# WINGS_SIGNAL_NODE_SCH.net
KiCad netlist of a schematic drawn in Altium Designer
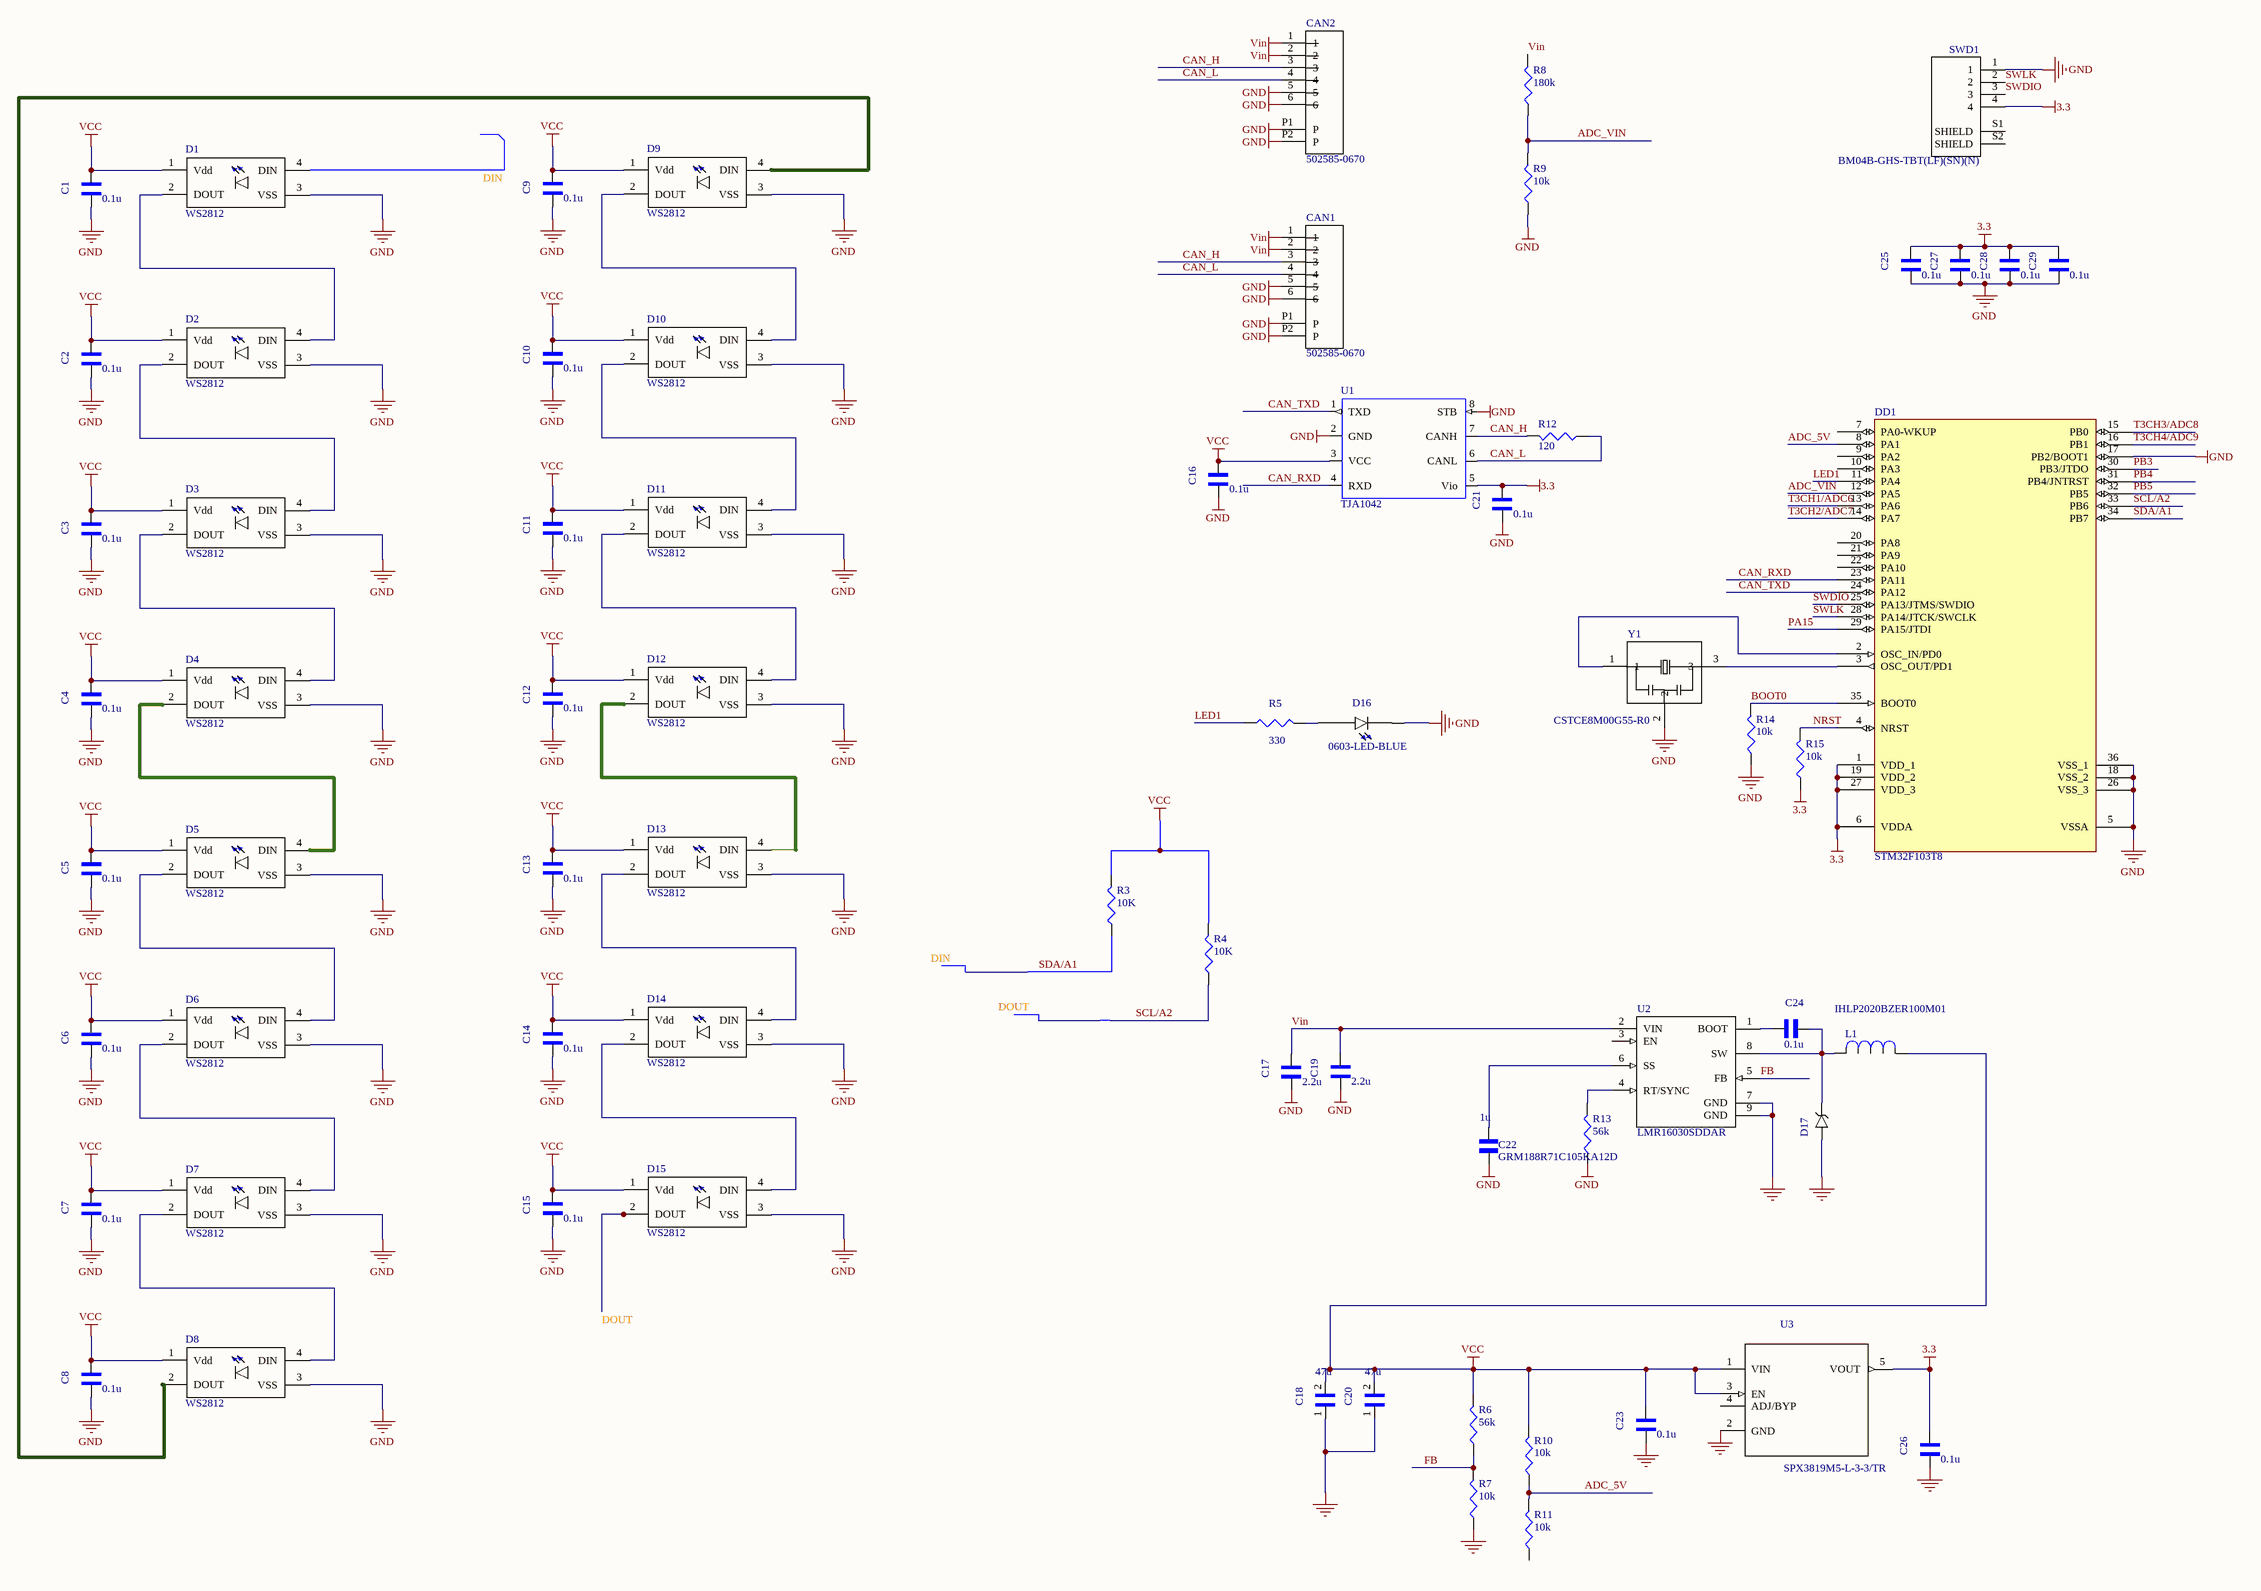
[diagram p0: WINGS_SIGNAL_NODE_SCH.SchDoc]

(export (version "E")
  (design (tool "Eeschema 10.0.6"))
  (components
    (comp (ref "C1")
      (value "0.1u")
      (footprint "*CAPC1608X90")
      (description "Cap Thin Film 0.1uf 50v 0603")
      (fields (field (name "MF") "AVX") (field (name "MP") "GX035C104MAT2-500 or CL10B104JB8NNNC"))
      (libsource (lib "lib") (part "GX035C104MAT2-500"))
    )
    (comp (ref "C2")
      (value "0.1u")
      (footprint "*CAPC1608X90")
      (description "Cap Thin Film 0.1uf 50v 0603")
      (fields (field (name "MF") "AVX") (field (name "MP") "GX035C104MAT2-500 or CL10B104JB8NNNC"))
      (libsource (lib "lib") (part "GX035C104MAT2-500"))
    )
    (comp (ref "C3")
      (value "0.1u")
      (footprint "*CAPC1608X90")
      (description "Cap Thin Film 0.1uf 50v 0603")
      (fields (field (name "MF") "AVX") (field (name "MP") "GX035C104MAT2-500 or CL10B104JB8NNNC"))
      (libsource (lib "lib") (part "GX035C104MAT2-500"))
    )
    (comp (ref "C4")
      (value "0.1u")
      (footprint "*CAPC1608X90")
      (description "Cap Thin Film 0.1uf 50v 0603")
      (fields (field (name "MF") "AVX") (field (name "MP") "GX035C104MAT2-500 or CL10B104JB8NNNC"))
      (libsource (lib "lib") (part "GX035C104MAT2-500"))
    )
    (comp (ref "C5")
      (value "0.1u")
      (footprint "*CAPC1608X90")
      (description "Cap Thin Film 0.1uf 50v 0603")
      (fields (field (name "MF") "AVX") (field (name "MP") "GX035C104MAT2-500 or CL10B104JB8NNNC"))
      (libsource (lib "lib") (part "GX035C104MAT2-500"))
    )
    (comp (ref "C6")
      (value "0.1u")
      (footprint "*CAPC1608X90")
      (description "Cap Thin Film 0.1uf 50v 0603")
      (fields (field (name "MF") "AVX") (field (name "MP") "GX035C104MAT2-500 or CL10B104JB8NNNC"))
      (libsource (lib "lib") (part "GX035C104MAT2-500"))
    )
    (comp (ref "C7")
      (value "0.1u")
      (footprint "*CAPC1608X90")
      (description "Cap Thin Film 0.1uf 50v 0603")
      (fields (field (name "MF") "AVX") (field (name "MP") "GX035C104MAT2-500 or CL10B104JB8NNNC"))
      (libsource (lib "lib") (part "GX035C104MAT2-500"))
    )
    (comp (ref "C8")
      (value "0.1u")
      (footprint "*CAPC1608X90")
      (description "Cap Thin Film 0.1uf 50v 0603")
      (fields (field (name "MF") "AVX") (field (name "MP") "GX035C104MAT2-500 or CL10B104JB8NNNC"))
      (libsource (lib "lib") (part "GX035C104MAT2-500"))
    )
    (comp (ref "C9")
      (value "0.1u")
      (footprint "*CAPC1608X90")
      (description "Cap Thin Film 0.1uf 50v 0603")
      (fields (field (name "MF") "AVX") (field (name "MP") "GX035C104MAT2-500 or CL10B104JB8NNNC"))
      (libsource (lib "lib") (part "GX035C104MAT2-500"))
    )
    (comp (ref "C10")
      (value "0.1u")
      (footprint "*CAPC1608X90")
      (description "Cap Thin Film 0.1uf 50v 0603")
      (fields (field (name "MF") "AVX") (field (name "MP") "GX035C104MAT2-500 or CL10B104JB8NNNC"))
      (libsource (lib "lib") (part "GX035C104MAT2-500"))
    )
    (comp (ref "C11")
      (value "0.1u")
      (footprint "*CAPC1608X90")
      (description "Cap Thin Film 0.1uf 50v 0603")
      (fields (field (name "MF") "AVX") (field (name "MP") "GX035C104MAT2-500 or CL10B104JB8NNNC"))
      (libsource (lib "lib") (part "GX035C104MAT2-500"))
    )
    (comp (ref "C12")
      (value "0.1u")
      (footprint "*CAPC1608X90")
      (description "Cap Thin Film 0.1uf 50v 0603")
      (fields (field (name "MF") "AVX") (field (name "MP") "GX035C104MAT2-500 or CL10B104JB8NNNC"))
      (libsource (lib "lib") (part "GX035C104MAT2-500"))
    )
    (comp (ref "C13")
      (value "0.1u")
      (footprint "*CAPC1608X90")
      (description "Cap Thin Film 0.1uf 50v 0603")
      (fields (field (name "MF") "AVX") (field (name "MP") "GX035C104MAT2-500 or CL10B104JB8NNNC"))
      (libsource (lib "lib") (part "GX035C104MAT2-500"))
    )
    (comp (ref "C14")
      (value "0.1u")
      (footprint "*CAPC1608X90")
      (description "Cap Thin Film 0.1uf 50v 0603")
      (fields (field (name "MF") "AVX") (field (name "MP") "GX035C104MAT2-500 or CL10B104JB8NNNC"))
      (libsource (lib "lib") (part "GX035C104MAT2-500"))
    )
    (comp (ref "C15")
      (value "0.1u")
      (footprint "*CAPC1608X90")
      (description "Cap Thin Film 0.1uf 50v 0603")
      (fields (field (name "MF") "AVX") (field (name "MP") "GX035C104MAT2-500 or CL10B104JB8NNNC"))
      (libsource (lib "lib") (part "GX035C104MAT2-500"))
    )
    (comp (ref "C16")
      (value "0.1u")
      (footprint "*CAPC1608X90")
      (description "Cap Thin Film 0.1uf 50v 0603")
      (fields (field (name "MF") "AVX") (field (name "MP") "GX035C104MAT2-500 or CL10B104JB8NNNC"))
      (libsource (lib "lib") (part "GX035C104MAT2-500"))
    )
    (comp (ref "C17")
      (value "2.2u")
      (footprint "*CAP3216X125N")
      (description "1206 2.2 uF 50 V В±10% Tolerance X7R SMT Multilayer Ceramic Capacitor")
      (fields (field (name "MF") "Murata Electronics") (field (name "MP") "GRM31CR71H225KA88L"))
      (libsource (lib "lib") (part "GRM31CR71H225KA88L"))
    )
    (comp (ref "C18")
      (value "47u")
      (footprint "*CAPC3216X125N")
      (description "Multilayer Ceramic Capacitor, GRM Series, 47 - F, - 10%, X5R, 10 V, 1206 [3216 Metric]")
      (fields (field (name "MF") "Murata Electronics") (field (name "MP") "GRM31CR61A476KE15L"))
      (libsource (lib "lib") (part "GRM31CR61A476KE15L"))
    )
    (comp (ref "C19")
      (value "2.2u")
      (footprint "*CAP3216X125N")
      (description "1206 2.2 uF 50 V В±10% Tolerance X7R SMT Multilayer Ceramic Capacitor")
      (fields (field (name "MF") "Murata Electronics") (field (name "MP") "GRM31CR71H225KA88L"))
      (libsource (lib "lib") (part "GRM31CR71H225KA88L"))
    )
    (comp (ref "C20")
      (value "47u")
      (footprint "*CAPC3216X125N")
      (description "Multilayer Ceramic Capacitor, GRM Series, 47 - F, - 10%, X5R, 10 V, 1206 [3216 Metric]")
      (fields (field (name "MF") "Murata Electronics") (field (name "MP") "GRM31CR61A476KE15L"))
      (libsource (lib "lib") (part "GRM31CR61A476KE15L"))
    )
    (comp (ref "C21")
      (value "0.1u")
      (footprint "*CAPC1608X90")
      (description "Cap Thin Film 0.1uf 50v 0603")
      (fields (field (name "MF") "AVX") (field (name "MP") "GX035C104MAT2-500 or CL10B104JB8NNNC"))
      (libsource (lib "lib") (part "GX035C104MAT2-500"))
    )
    (comp (ref "C22")
      (value "GRM188R71C105KA12D")
      (footprint "CAPC1608X90N")
      (description "SMD Capacitor X7R(EIA) with Capacitance: 1.0uF Tol. 10%. Rated Voltage: 16Vdc")
      (fields (field (name "MF") "Murata Electronics") (field (name "ALTIUM_VALUE") "1u"))
      (libsource (lib "lib") (part "GRM188R71C105KA12D"))
    )
    (comp (ref "C23")
      (value "0.1u")
      (footprint "*CAPC1608X90")
      (description "Cap Thin Film 0.1uf 50v 0603")
      (fields (field (name "MF") "AVX") (field (name "MP") "GX035C104MAT2-500"))
      (libsource (lib "lib") (part "GX035C104MAT2-500"))
    )
    (comp (ref "C24")
      (value "0.1u")
      (footprint "*CAPC1608X90")
      (description "Cap Thin Film 0.1uf 50v 0603")
      (fields (field (name "MF") "AVX") (field (name "MP") "GX035C104MAT2-500 or CL10B104JB8NNNC"))
      (libsource (lib "lib") (part "GX035C104MAT2-500"))
    )
    (comp (ref "C25")
      (value "0.1u")
      (footprint "*CAPC1608X90")
      (description "Cap Thin Film 0.1uf 50v 0603")
      (fields (field (name "MF") "AVX") (field (name "MP") "GX035C104MAT2-500 or CL10B104JB8NNNC"))
      (libsource (lib "lib") (part "GX035C104MAT2-500"))
    )
    (comp (ref "C26")
      (value "0.1u")
      (footprint "*CAPC1608X90")
      (description "Cap Thin Film 0.1uf 50v 0603")
      (fields (field (name "MF") "AVX") (field (name "MP") "GX035C104MAT2-500"))
      (libsource (lib "lib") (part "GX035C104MAT2-500"))
    )
    (comp (ref "C27")
      (value "0.1u")
      (footprint "*CAPC1608X90")
      (description "Cap Thin Film 0.1uf 50v 0603")
      (fields (field (name "MF") "AVX") (field (name "MP") "GX035C104MAT2-500 or CL10B104JB8NNNC"))
      (libsource (lib "lib") (part "GX035C104MAT2-500"))
    )
    (comp (ref "C28")
      (value "0.1u")
      (footprint "*CAPC1608X90")
      (description "Cap Thin Film 0.1uf 50v 0603")
      (fields (field (name "MF") "AVX") (field (name "MP") "GX035C104MAT2-500 or CL10B104JB8NNNC"))
      (libsource (lib "lib") (part "GX035C104MAT2-500"))
    )
    (comp (ref "C29")
      (value "0.1u")
      (footprint "*CAPC1608X90")
      (description "Cap Thin Film 0.1uf 50v 0603")
      (fields (field (name "MF") "AVX") (field (name "MP") "GX035C104MAT2-500 or CL10B104JB8NNNC"))
      (libsource (lib "lib") (part "GX035C104MAT2-500"))
    )
    (comp (ref "CAN1")
      (value "502585-0670")
      (footprint "MOLEX_502585-0670")
      (fields (field (name "MF") "Molex"))
      (libsource (lib "lib") (part "502585-0670"))
    )
    (comp (ref "CAN2")
      (value "502585-0670")
      (footprint "MOLEX_502585-0670")
      (fields (field (name "MF") "Molex"))
      (libsource (lib "lib") (part "502585-0670"))
    )
    (comp (ref "D1")
      (value "WS2812")
      (footprint "LED_WS2812")
      (description "Addressable Lighting - 5 LED Discrete Serial _Shift Register_ Red, Green, Blue _RGB_ 5.00mm Dia")
      (fields (field (name "MF") "SparkFun Electronics"))
      (libsource (lib "lib") (part "WS2812"))
    )
    (comp (ref "D2")
      (value "WS2812")
      (footprint "LED_WS2812")
      (description "Addressable Lighting - 5 LED Discrete Serial _Shift Register_ Red, Green, Blue _RGB_ 5.00mm Dia")
      (fields (field (name "MF") "SparkFun Electronics"))
      (libsource (lib "lib") (part "WS2812"))
    )
    (comp (ref "D3")
      (value "WS2812")
      (footprint "LED_WS2812")
      (description "Addressable Lighting - 5 LED Discrete Serial _Shift Register_ Red, Green, Blue _RGB_ 5.00mm Dia")
      (fields (field (name "MF") "SparkFun Electronics"))
      (libsource (lib "lib") (part "WS2812"))
    )
    (comp (ref "D4")
      (value "WS2812")
      (footprint "LED_WS2812")
      (description "Addressable Lighting - 5 LED Discrete Serial _Shift Register_ Red, Green, Blue _RGB_ 5.00mm Dia")
      (fields (field (name "MF") "SparkFun Electronics"))
      (libsource (lib "lib") (part "WS2812"))
    )
    (comp (ref "D5")
      (value "WS2812")
      (footprint "LED_WS2812")
      (description "Addressable Lighting - 5 LED Discrete Serial _Shift Register_ Red, Green, Blue _RGB_ 5.00mm Dia")
      (fields (field (name "MF") "SparkFun Electronics"))
      (libsource (lib "lib") (part "WS2812"))
    )
    (comp (ref "D6")
      (value "WS2812")
      (footprint "LED_WS2812")
      (description "Addressable Lighting - 5 LED Discrete Serial _Shift Register_ Red, Green, Blue _RGB_ 5.00mm Dia")
      (fields (field (name "MF") "SparkFun Electronics"))
      (libsource (lib "lib") (part "WS2812"))
    )
    (comp (ref "D7")
      (value "WS2812")
      (footprint "LED_WS2812")
      (description "Addressable Lighting - 5 LED Discrete Serial _Shift Register_ Red, Green, Blue _RGB_ 5.00mm Dia")
      (fields (field (name "MF") "SparkFun Electronics"))
      (libsource (lib "lib") (part "WS2812"))
    )
    (comp (ref "D8")
      (value "WS2812")
      (footprint "LED_WS2812")
      (description "Addressable Lighting - 5 LED Discrete Serial _Shift Register_ Red, Green, Blue _RGB_ 5.00mm Dia")
      (fields (field (name "MF") "SparkFun Electronics"))
      (libsource (lib "lib") (part "WS2812"))
    )
    (comp (ref "D9")
      (value "WS2812")
      (footprint "LED_WS2812")
      (description "Addressable Lighting - 5 LED Discrete Serial _Shift Register_ Red, Green, Blue _RGB_ 5.00mm Dia")
      (fields (field (name "MF") "SparkFun Electronics"))
      (libsource (lib "lib") (part "WS2812"))
    )
    (comp (ref "D10")
      (value "WS2812")
      (footprint "LED_WS2812")
      (description "Addressable Lighting - 5 LED Discrete Serial _Shift Register_ Red, Green, Blue _RGB_ 5.00mm Dia")
      (fields (field (name "MF") "SparkFun Electronics"))
      (libsource (lib "lib") (part "WS2812"))
    )
    (comp (ref "D11")
      (value "WS2812")
      (footprint "LED_WS2812")
      (description "Addressable Lighting - 5 LED Discrete Serial _Shift Register_ Red, Green, Blue _RGB_ 5.00mm Dia")
      (fields (field (name "MF") "SparkFun Electronics"))
      (libsource (lib "lib") (part "WS2812"))
    )
    (comp (ref "D12")
      (value "WS2812")
      (footprint "LED_WS2812")
      (description "Addressable Lighting - 5 LED Discrete Serial _Shift Register_ Red, Green, Blue _RGB_ 5.00mm Dia")
      (fields (field (name "MF") "SparkFun Electronics"))
      (libsource (lib "lib") (part "WS2812"))
    )
    (comp (ref "D13")
      (value "WS2812")
      (footprint "LED_WS2812")
      (description "Addressable Lighting - 5 LED Discrete Serial _Shift Register_ Red, Green, Blue _RGB_ 5.00mm Dia")
      (fields (field (name "MF") "SparkFun Electronics"))
      (libsource (lib "lib") (part "WS2812"))
    )
    (comp (ref "D14")
      (value "WS2812")
      (footprint "LED_WS2812")
      (description "Addressable Lighting - 5 LED Discrete Serial _Shift Register_ Red, Green, Blue _RGB_ 5.00mm Dia")
      (fields (field (name "MF") "SparkFun Electronics"))
      (libsource (lib "lib") (part "WS2812"))
    )
    (comp (ref "D15")
      (value "WS2812")
      (footprint "LED_WS2812")
      (description "Addressable Lighting - 5 LED Discrete Serial _Shift Register_ Red, Green, Blue _RGB_ 5.00mm Dia")
      (fields (field (name "MF") "SparkFun Electronics"))
      (libsource (lib "lib") (part "WS2812"))
    )
    (comp (ref "D16")
      (value "0603-LED-BLUE")
      (footprint "*LEDM1608X80_LTE-C1906R-14(Primary)")
      (description "LED IrLED Chip LED 2-Pin SMD T/R")
      (libsource (lib "lib") (part "LTE-C1906R-14"))
    )
    (comp (ref "D17")
      (value "SK56")
      (footprint "*SMB_P6SMB62AT3G(Primary)")
      (description "Диод Шоттки 5А 60В [SMB / DO-214AA]")
      (fields (field (name "MF") "Littelfuse Inc."))
      (libsource (lib "lib") (part "SK56"))
    )
    (comp (ref "DD1")
      (value "STM32F103T8")
      (footprint "*QFN50P600X600X100-37N")
      (description "STM32F103T8U6, Микроконтроллер 32BIT ARM 64K FLASH [VFQFPN-36]")
      (fields (field (name "MF") "STM") (field (name "MP") "STM32F103T8U6"))
      (libsource (lib "lib") (part "STM32F103T8"))
    )
    (comp (ref "L1")
      (value "IHLP2020BZER100M01")
      (footprint "IHLP")
      (description "10ÂµH Shielded Molded Inductor 2.3A 199mOhm Max Nonstandard")
      (fields (field (name "MF") "Vishay Dale"))
      (libsource (lib "lib") (part "IHLP2020BZER100M01"))
    )
    (comp (ref "R3")
      (value "10K")
      (footprint "J1-0603")
      (description "Resistor")
      (fields (field (name "MP") "4.7K 1% 0603") (field (name "Comment") "Res3"))
      (libsource (lib "Miscellaneous Devices") (part "Res3"))
    )
    (comp (ref "R4")
      (value "10K")
      (footprint "J1-0603")
      (description "Resistor")
      (fields (field (name "MP") "4.7K 1% 0603") (field (name "Comment") "Res3"))
      (libsource (lib "Miscellaneous Devices") (part "Res3"))
    )
    (comp (ref "R5")
      (value "330")
      (footprint "J1-0603")
      (description "Resistor")
      (fields (field (name "MP") "RC0603FR-07330RL") (field (name "Comment") "Res3"))
      (libsource (lib "Miscellaneous Devices") (part "Res3"))
    )
    (comp (ref "R6")
      (value "56k")
      (footprint "J1-0603")
      (description "Resistor")
      (fields (field (name "MP") "RC0603FR-0756KL") (field (name "Comment") "Res3"))
      (libsource (lib "Miscellaneous Devices") (part "Res3"))
    )
    (comp (ref "R7")
      (value "10k")
      (footprint "J1-0603")
      (description "10 kOhms 1 0.1 W 1 10 W Chip Resistor 0603 1608 Metric Thick Film")
      (fields (field (name "MF") "Yageo or NXP") (field (name "MP") "10K 1% 0603"))
      (libsource (lib "CAN_NODE_MINI") (part "RC0603FR-0710KL"))
    )
    (comp (ref "R8")
      (value "180k")
      (footprint "J1-0603")
      (description "Resistor")
      (fields (field (name "MP") "180K 1% 0603") (field (name "Comment") "Res3"))
      (libsource (lib "Miscellaneous Devices") (part "Res3"))
    )
    (comp (ref "R9")
      (value "10k")
      (footprint "J1-0603")
      (description "Resistor")
      (fields (field (name "MP") "10K 1% 0603") (field (name "Comment") "Res3"))
      (libsource (lib "Miscellaneous Devices") (part "Res3"))
    )
    (comp (ref "R10")
      (value "10k")
      (footprint "J1-0603")
      (description "10 kOhms 1 0.1 W 1 10 W Chip Resistor 0603 1608 Metric Thick Film")
      (fields (field (name "MF") "Yageo or NXP") (field (name "MP") "10K 1% 0603"))
      (libsource (lib "CAN_NODE_MINI") (part "RC0603FR-0710KL"))
    )
    (comp (ref "R11")
      (value "10k")
      (footprint "J1-0603")
      (description "10 kOhms 1 0.1 W 1 10 W Chip Resistor 0603 1608 Metric Thick Film")
      (fields (field (name "MF") "Yageo or NXP") (field (name "MP") "10K 1% 0603"))
      (libsource (lib "CAN_NODE_MINI") (part "RC0603FR-0710KL"))
    )
    (comp (ref "R12")
      (value "120")
      (footprint "J1-0603")
      (description "120 Ohms 1 0.1 W 1 10 W Chip Resistor 0603 1608 Metric Thick Film")
      (fields (field (name "MP") "RC0603FR-07120RL") (field (name "Comment") "Res3"))
      (libsource (lib "Miscellaneous Devices") (part "Res3"))
    )
    (comp (ref "R13")
      (value "56k")
      (footprint "J1-0603")
      (description "Resistor")
      (fields (field (name "MP") "RC0603FR-0756KL") (field (name "Comment") "Res3"))
      (libsource (lib "Miscellaneous Devices") (part "Res3"))
    )
    (comp (ref "R14")
      (value "10k")
      (footprint "J1-0603")
      (description "10 kOhms 1 0.1 W 1 10 W Chip Resistor 0603 1608 Metric Thick Film")
      (fields (field (name "MF") "Yageo or NXP") (field (name "MP") "10K 1% 0603"))
      (libsource (lib "CAN_NODE_MINI") (part "RC0603FR-0710KL"))
    )
    (comp (ref "R15")
      (value "10k")
      (footprint "J1-0603")
      (description "10 kOhms 1 0.1 W 1 10 W Chip Resistor 0603 1608 Metric Thick Film")
      (fields (field (name "MF") "Yageo or NXP") (field (name "MP") "10K 1% 0603"))
      (libsource (lib "CAN_NODE_MINI") (part "RC0603FR-0710KL"))
    )
    (comp (ref "SWD1")
      (value "BM04B-GHS-TBT(LF)(SN)(N)")
      (footprint "JST_BM04B-GHS-holes")
      (description "Conn Shrouded Header HDR 4 POS 1.25mm Solder ST SMD Reel")
      (fields (field (name "MF") "JST Sales") (field (name "MP") "SM04B-GHS-TB(LF)(SN)"))
      (libsource (lib "lib") (part "BM04B-GHS-TBT(LF)(SN)(N)"))
    )
    (comp (ref "U1")
      (value "TJA1042")
      (footprint "SOT782-1")
      (description "1/1 Transceiver Half CANbus 8-SO")
      (fields (field (name "MF") "NXP USA"))
      (libsource (lib "lib") (part "TJA1042"))
    )
    (comp (ref "U2")
      (value "LMR16030SDDAR")
      (footprint "*SOIC127P600X170-9N - duplicate")
      (fields (field (name "MF") "Texas Instruments"))
      (libsource (lib "lib") (part "LMR16030SDDAR"))
    )
    (comp (ref "U3")
      (value "SPX3819M5-L-3-3/TR")
      (footprint "*SOT95P280X145-5N")
      (description "Low Dropout Voltage Regulator, Adjustable 0.5A, В±1%, 2.5 to 16 Vin, 5-Pin SOT-23")
      (fields (field (name "MF") "MaxLinear, Inc."))
      (libsource (lib "DC_DC") (part "SPX3819M5-L"))
    )
    (comp (ref "Y1")
      (value "CSTCE8M00G55-R0")
      (footprint "*OSC_CSTCE8M00G55-R0")
      (description "Ceramic Resonator 8MHz ??0.5% _Tol_ ??0.2% _Stability_ 33pF 40Ohm 3-Pin CSMD T/R")
      (fields (field (name "MF") "Murata"))
      (libsource (lib "DC_DC") (part "CSTCE8M00G55-R0"))
    )
  )
  (nets
    (net (code "1") (name "/ADC_5V") (class "Default")
      (node (ref "DD1") (pin "8") (pinfunction "PA1_8") (pintype "bidirectional"))
      (node (ref "R10") (pin "1") (pinfunction "1_1") (pintype "passive"))
      (node (ref "R11") (pin "2") (pinfunction "2_2") (pintype "passive"))
    )
    (net (code "2") (name "/ADC_VIN") (class "Default")
      (node (ref "DD1") (pin "12") (pinfunction "PA5_12") (pintype "bidirectional"))
      (node (ref "R8") (pin "1") (pinfunction "1_1") (pintype "passive"))
      (node (ref "R9") (pin "2") (pinfunction "2_2") (pintype "passive"))
    )
    (net (code "3") (name "/BOOT0") (class "Default")
      (node (ref "DD1") (pin "35") (pinfunction "BOOT0_35") (pintype "input"))
      (node (ref "R14") (pin "2") (pinfunction "2_2") (pintype "passive"))
    )
    (net (code "4") (name "/CAN_H") (class "Default")
      (node (ref "CAN1") (pin "3") (pinfunction "3_3") (pintype "passive"))
      (node (ref "CAN2") (pin "3") (pinfunction "3_3") (pintype "passive"))
      (node (ref "R12") (pin "2") (pinfunction "2_2") (pintype "passive"))
      (node (ref "U1") (pin "7") (pinfunction "CANH_7") (pintype "bidirectional"))
    )
    (net (code "5") (name "/CAN_L") (class "Default")
      (node (ref "CAN1") (pin "4") (pinfunction "4_4") (pintype "passive"))
      (node (ref "CAN2") (pin "4") (pinfunction "4_4") (pintype "passive"))
      (node (ref "R12") (pin "1") (pinfunction "1_1") (pintype "passive"))
      (node (ref "U1") (pin "6") (pinfunction "CANL_6") (pintype "bidirectional"))
    )
    (net (code "6") (name "/CAN_RXD") (class "Default")
      (node (ref "DD1") (pin "23") (pinfunction "PA11_23") (pintype "bidirectional"))
      (node (ref "U1") (pin "4") (pinfunction "RXD_4") (pintype "bidirectional"))
    )
    (net (code "7") (name "/CAN_TXD") (class "Default")
      (node (ref "DD1") (pin "24") (pinfunction "PA12_24") (pintype "bidirectional"))
      (node (ref "U1") (pin "1") (pinfunction "TXD_1") (pintype "output"))
    )
    (net (code "8") (name "/DIN") (class "Default")
      (node (ref "D1") (pin "4") (pinfunction "DIN_4") (pintype "power_in"))
      (node (ref "DD1") (pin "34") (pinfunction "PB7_34") (pintype "bidirectional"))
      (node (ref "R3") (pin "1") (pinfunction "1_1") (pintype "passive"))
    )
    (net (code "9") (name "/DOUT") (class "Default")
      (node (ref "D15") (pin "2") (pinfunction "DOUT_2") (pintype "power_in"))
      (node (ref "DD1") (pin "33") (pinfunction "PB6_33") (pintype "bidirectional"))
      (node (ref "R4") (pin "1") (pinfunction "1_1") (pintype "passive"))
    )
    (net (code "10") (name "/FB") (class "Default")
      (node (ref "R6") (pin "1") (pinfunction "1_1") (pintype "passive"))
      (node (ref "R7") (pin "2") (pinfunction "2_2") (pintype "passive"))
      (node (ref "U2") (pin "5") (pinfunction "FB_5") (pintype "input"))
    )
    (net (code "11") (name "/LED1") (class "Default")
      (node (ref "DD1") (pin "11") (pinfunction "PA4_11") (pintype "bidirectional"))
      (node (ref "R5") (pin "1") (pinfunction "1_1") (pintype "passive"))
    )
    (net (code "12") (name "/NRST") (class "Default")
      (node (ref "DD1") (pin "4") (pinfunction "NRST_4") (pintype "bidirectional"))
      (node (ref "R15") (pin "2") (pinfunction "2_2") (pintype "passive"))
    )
    (net (code "13") (name "/PA15") (class "Default")
      (node (ref "DD1") (pin "29") (pinfunction "PA15/JTDI_29") (pintype "bidirectional"))
    )
    (net (code "14") (name "/PB3") (class "Default")
      (node (ref "DD1") (pin "30") (pinfunction "PB3/JTDO_30") (pintype "bidirectional"))
    )
    (net (code "15") (name "/PB4") (class "Default")
      (node (ref "DD1") (pin "31") (pinfunction "PB4/JNTRST_31") (pintype "bidirectional"))
    )
    (net (code "16") (name "/PB5") (class "Default")
      (node (ref "DD1") (pin "32") (pinfunction "PB5_32") (pintype "bidirectional"))
    )
    (net (code "17") (name "/SWDIO") (class "Default")
      (node (ref "DD1") (pin "25") (pinfunction "PA13/JTMS/SWDIO_25") (pintype "bidirectional"))
      (node (ref "SWD1") (pin "3") (pinfunction "3_3") (pintype "passive"))
    )
    (net (code "18") (name "/SWLK") (class "Default")
      (node (ref "DD1") (pin "28") (pinfunction "PA14/JTCK/SWCLK_28") (pintype "bidirectional"))
      (node (ref "SWD1") (pin "2") (pinfunction "2_2") (pintype "passive"))
    )
    (net (code "19") (name "/T3CH1{slash}ADC6") (class "Default")
      (node (ref "DD1") (pin "13") (pinfunction "PA6_13") (pintype "bidirectional"))
    )
    (net (code "20") (name "/T3CH2{slash}ADC7") (class "Default")
      (node (ref "DD1") (pin "14") (pinfunction "PA7_14") (pintype "bidirectional"))
    )
    (net (code "21") (name "/T3CH3{slash}ADC8") (class "Default")
      (node (ref "DD1") (pin "15") (pinfunction "PB0_15") (pintype "bidirectional"))
    )
    (net (code "22") (name "/T3CH4{slash}ADC9") (class "Default")
      (node (ref "DD1") (pin "16") (pinfunction "PB1_16") (pintype "bidirectional"))
    )
    (net (code "23") (name "3.3") (class "Default")
      (node (ref "C21") (pin "1") (pinfunction "1_1") (pintype "passive"))
      (node (ref "C25") (pin "1") (pinfunction "1_1") (pintype "passive"))
      (node (ref "C26") (pin "1") (pinfunction "1_1") (pintype "passive"))
      (node (ref "C27") (pin "1") (pinfunction "1_1") (pintype "passive"))
      (node (ref "C28") (pin "1") (pinfunction "1_1") (pintype "passive"))
      (node (ref "C29") (pin "1") (pinfunction "1_1") (pintype "passive"))
      (node (ref "DD1") (pin "1") (pinfunction "VDD_1_1") (pintype "power_in"))
      (node (ref "DD1") (pin "19") (pinfunction "VDD_2_19") (pintype "power_in"))
      (node (ref "DD1") (pin "27") (pinfunction "VDD_3_27") (pintype "power_in"))
      (node (ref "DD1") (pin "6") (pinfunction "VDDA_6") (pintype "power_in"))
      (node (ref "R15") (pin "1") (pinfunction "1_1") (pintype "passive"))
      (node (ref "SWD1") (pin "4") (pinfunction "4_4") (pintype "passive"))
      (node (ref "U1") (pin "5") (pinfunction "Vio_5") (pintype "power_in"))
      (node (ref "U3") (pin "5") (pinfunction "VOUT_5") (pintype "output"))
    )
    (net (code "24") (name "GND") (class "Default")
      (node (ref "C1") (pin "2") (pinfunction "2_2") (pintype "passive"))
      (node (ref "C10") (pin "2") (pinfunction "2_2") (pintype "passive"))
      (node (ref "C11") (pin "2") (pinfunction "2_2") (pintype "passive"))
      (node (ref "C12") (pin "2") (pinfunction "2_2") (pintype "passive"))
      (node (ref "C13") (pin "2") (pinfunction "2_2") (pintype "passive"))
      (node (ref "C14") (pin "2") (pinfunction "2_2") (pintype "passive"))
      (node (ref "C15") (pin "2") (pinfunction "2_2") (pintype "passive"))
      (node (ref "C16") (pin "2") (pinfunction "2_2") (pintype "passive"))
      (node (ref "C17") (pin "2") (pinfunction "2_2") (pintype "passive"))
      (node (ref "C18") (pin "1") (pinfunction "1_1") (pintype "passive"))
      (node (ref "C19") (pin "2") (pinfunction "2_2") (pintype "passive"))
      (node (ref "C2") (pin "2") (pinfunction "2_2") (pintype "passive"))
      (node (ref "C20") (pin "1") (pinfunction "1_1") (pintype "passive"))
      (node (ref "C21") (pin "2") (pinfunction "2_2") (pintype "passive"))
      (node (ref "C22") (pin "1") (pinfunction "1_1") (pintype "passive"))
      (node (ref "C23") (pin "2") (pinfunction "2_2") (pintype "passive"))
      (node (ref "C25") (pin "2") (pinfunction "2_2") (pintype "passive"))
      (node (ref "C26") (pin "2") (pinfunction "2_2") (pintype "passive"))
      (node (ref "C27") (pin "2") (pinfunction "2_2") (pintype "passive"))
      (node (ref "C28") (pin "2") (pinfunction "2_2") (pintype "passive"))
      (node (ref "C29") (pin "2") (pinfunction "2_2") (pintype "passive"))
      (node (ref "C3") (pin "2") (pinfunction "2_2") (pintype "passive"))
      (node (ref "C4") (pin "2") (pinfunction "2_2") (pintype "passive"))
      (node (ref "C5") (pin "2") (pinfunction "2_2") (pintype "passive"))
      (node (ref "C6") (pin "2") (pinfunction "2_2") (pintype "passive"))
      (node (ref "C7") (pin "2") (pinfunction "2_2") (pintype "passive"))
      (node (ref "C8") (pin "2") (pinfunction "2_2") (pintype "passive"))
      (node (ref "C9") (pin "2") (pinfunction "2_2") (pintype "passive"))
      (node (ref "CAN1") (pin "5") (pinfunction "5_5") (pintype "passive"))
      (node (ref "CAN1") (pin "6") (pinfunction "6_6") (pintype "passive"))
      (node (ref "CAN1") (pin "P1") (pinfunction "P_P1") (pintype "passive"))
      (node (ref "CAN1") (pin "P2") (pinfunction "P_P2") (pintype "passive"))
      (node (ref "CAN2") (pin "5") (pinfunction "5_5") (pintype "passive"))
      (node (ref "CAN2") (pin "6") (pinfunction "6_6") (pintype "passive"))
      (node (ref "CAN2") (pin "P1") (pinfunction "P_P1") (pintype "passive"))
      (node (ref "CAN2") (pin "P2") (pinfunction "P_P2") (pintype "passive"))
      (node (ref "D1") (pin "3") (pinfunction "VSS_3") (pintype "power_in"))
      (node (ref "D10") (pin "3") (pinfunction "VSS_3") (pintype "power_in"))
      (node (ref "D11") (pin "3") (pinfunction "VSS_3") (pintype "power_in"))
      (node (ref "D12") (pin "3") (pinfunction "VSS_3") (pintype "power_in"))
      (node (ref "D13") (pin "3") (pinfunction "VSS_3") (pintype "power_in"))
      (node (ref "D14") (pin "3") (pinfunction "VSS_3") (pintype "power_in"))
      (node (ref "D15") (pin "3") (pinfunction "VSS_3") (pintype "power_in"))
      (node (ref "D16") (pin "C") (pinfunction "C_C") (pintype "passive"))
      (node (ref "D17") (pin "A") (pinfunction "A_A") (pintype "power_in"))
      (node (ref "D2") (pin "3") (pinfunction "VSS_3") (pintype "power_in"))
      (node (ref "D3") (pin "3") (pinfunction "VSS_3") (pintype "power_in"))
      (node (ref "D4") (pin "3") (pinfunction "VSS_3") (pintype "power_in"))
      (node (ref "D5") (pin "3") (pinfunction "VSS_3") (pintype "power_in"))
      (node (ref "D6") (pin "3") (pinfunction "VSS_3") (pintype "power_in"))
      (node (ref "D7") (pin "3") (pinfunction "VSS_3") (pintype "power_in"))
      (node (ref "D8") (pin "3") (pinfunction "VSS_3") (pintype "power_in"))
      (node (ref "D9") (pin "3") (pinfunction "VSS_3") (pintype "power_in"))
      (node (ref "DD1") (pin "17") (pinfunction "PB2/BOOT1_17") (pintype "bidirectional"))
      (node (ref "DD1") (pin "18") (pinfunction "VSS_2_18") (pintype "power_in"))
      (node (ref "DD1") (pin "26") (pinfunction "VSS_3_26") (pintype "power_in"))
      (node (ref "DD1") (pin "36") (pinfunction "VSS_1_36") (pintype "power_in"))
      (node (ref "DD1") (pin "5") (pinfunction "VSSA_5") (pintype "power_in"))
      (node (ref "R13") (pin "1") (pinfunction "1_1") (pintype "passive"))
      (node (ref "R14") (pin "1") (pinfunction "1_1") (pintype "passive"))
      (node (ref "R7") (pin "1") (pinfunction "1_1") (pintype "passive"))
      (node (ref "R9") (pin "1") (pinfunction "1_1") (pintype "passive"))
      (node (ref "SWD1") (pin "1") (pinfunction "1_1") (pintype "passive"))
      (node (ref "U1") (pin "2") (pinfunction "GND_2") (pintype "power_in"))
      (node (ref "U1") (pin "8") (pinfunction "STB_8") (pintype "input"))
      (node (ref "U2") (pin "7") (pinfunction "GND_7") (pintype "power_in"))
      (node (ref "U2") (pin "9") (pinfunction "GND_9") (pintype "power_in"))
      (node (ref "U3") (pin "2") (pinfunction "GND_2") (pintype "passive"))
      (node (ref "Y1") (pin "2") (pinfunction "2_2") (pintype "power_in"))
    )
    (net (code "25") (name "Net-(D1-DOUT)") (class "Default")
      (node (ref "D1") (pin "2") (pinfunction "DOUT_2") (pintype "power_in"))
      (node (ref "D2") (pin "4") (pinfunction "DIN_4") (pintype "power_in"))
    )
    (net (code "26") (name "Net-(D2-DOUT)") (class "Default")
      (node (ref "D2") (pin "2") (pinfunction "DOUT_2") (pintype "power_in"))
      (node (ref "D3") (pin "4") (pinfunction "DIN_4") (pintype "power_in"))
    )
    (net (code "27") (name "Net-(D3-DOUT)") (class "Default")
      (node (ref "D3") (pin "2") (pinfunction "DOUT_2") (pintype "power_in"))
      (node (ref "D4") (pin "4") (pinfunction "DIN_4") (pintype "power_in"))
    )
    (net (code "28") (name "Net-(D4-DOUT)") (class "Default")
      (node (ref "D4") (pin "2") (pinfunction "DOUT_2") (pintype "power_in"))
      (node (ref "D5") (pin "4") (pinfunction "DIN_4") (pintype "power_in"))
    )
    (net (code "29") (name "Net-(D5-DOUT)") (class "Default")
      (node (ref "D5") (pin "2") (pinfunction "DOUT_2") (pintype "power_in"))
      (node (ref "D6") (pin "4") (pinfunction "DIN_4") (pintype "power_in"))
    )
    (net (code "30") (name "Net-(D6-DOUT)") (class "Default")
      (node (ref "D6") (pin "2") (pinfunction "DOUT_2") (pintype "power_in"))
      (node (ref "D7") (pin "4") (pinfunction "DIN_4") (pintype "power_in"))
    )
    (net (code "31") (name "Net-(D7-DOUT)") (class "Default")
      (node (ref "D7") (pin "2") (pinfunction "DOUT_2") (pintype "power_in"))
      (node (ref "D8") (pin "4") (pinfunction "DIN_4") (pintype "power_in"))
    )
    (net (code "32") (name "Net-(D8-DOUT)") (class "Default")
      (node (ref "D8") (pin "2") (pinfunction "DOUT_2") (pintype "power_in"))
      (node (ref "D9") (pin "4") (pinfunction "DIN_4") (pintype "power_in"))
    )
    (net (code "33") (name "Net-(D10-DIN)") (class "Default")
      (node (ref "D10") (pin "4") (pinfunction "DIN_4") (pintype "power_in"))
      (node (ref "D9") (pin "2") (pinfunction "DOUT_2") (pintype "power_in"))
    )
    (net (code "34") (name "Net-(D10-DOUT)") (class "Default")
      (node (ref "D10") (pin "2") (pinfunction "DOUT_2") (pintype "power_in"))
      (node (ref "D11") (pin "4") (pinfunction "DIN_4") (pintype "power_in"))
    )
    (net (code "35") (name "Net-(D11-DOUT)") (class "Default")
      (node (ref "D11") (pin "2") (pinfunction "DOUT_2") (pintype "power_in"))
      (node (ref "D12") (pin "4") (pinfunction "DIN_4") (pintype "power_in"))
    )
    (net (code "36") (name "Net-(D12-DOUT)") (class "Default")
      (node (ref "D12") (pin "2") (pinfunction "DOUT_2") (pintype "power_in"))
      (node (ref "D13") (pin "4") (pinfunction "DIN_4") (pintype "power_in"))
    )
    (net (code "37") (name "Net-(D13-DOUT)") (class "Default")
      (node (ref "D13") (pin "2") (pinfunction "DOUT_2") (pintype "power_in"))
      (node (ref "D14") (pin "4") (pinfunction "DIN_4") (pintype "power_in"))
    )
    (net (code "38") (name "Net-(D14-DOUT)") (class "Default")
      (node (ref "D14") (pin "2") (pinfunction "DOUT_2") (pintype "power_in"))
      (node (ref "D15") (pin "4") (pinfunction "DIN_4") (pintype "power_in"))
    )
    (net (code "39") (name "Net-(D16-PadA)") (class "Default")
      (node (ref "D16") (pin "A") (pinfunction "A_A") (pintype "passive"))
      (node (ref "R5") (pin "2") (pinfunction "2_2") (pintype "passive"))
    )
    (net (code "40") (name "Net-(DD1-OSC_IN{slash}PD0)") (class "Default")
      (node (ref "DD1") (pin "2") (pinfunction "OSC_IN/PD0_2") (pintype "input"))
      (node (ref "Y1") (pin "1") (pinfunction "1_1") (pintype "passive"))
    )
    (net (code "41") (name "Net-(DD1-OSC_OUT{slash}PD1)") (class "Default")
      (node (ref "DD1") (pin "3") (pinfunction "OSC_OUT/PD1_3") (pintype "output"))
      (node (ref "Y1") (pin "3") (pinfunction "3_3") (pintype "passive"))
    )
    (net (code "42") (name "Net-(U2-BOOT)") (class "Default")
      (node (ref "C24") (pin "2") (pinfunction "2_2") (pintype "passive"))
      (node (ref "U2") (pin "1") (pinfunction "BOOT_1") (pintype "power_in"))
    )
    (net (code "43") (name "Net-(U2-RT{slash}SYNC)") (class "Default")
      (node (ref "R13") (pin "2") (pinfunction "2_2") (pintype "passive"))
      (node (ref "U2") (pin "4") (pinfunction "RT/SYNC_4") (pintype "input"))
    )
    (net (code "44") (name "Net-(U2-SS)") (class "Default")
      (node (ref "C22") (pin "2") (pinfunction "2_2") (pintype "passive"))
      (node (ref "U2") (pin "6") (pinfunction "SS_6") (pintype "input"))
    )
    (net (code "45") (name "Net-(U2-SW)") (class "Default")
      (node (ref "C24") (pin "1") (pinfunction "1_1") (pintype "passive"))
      (node (ref "D17") (pin "C") (pinfunction "C_C") (pintype "power_in"))
      (node (ref "L1") (pin "2") (pinfunction "2_2") (pintype "passive"))
      (node (ref "U2") (pin "8") (pinfunction "SW_8") (pintype "power_in"))
    )
    (net (code "46") (name "VCC") (class "Default")
      (node (ref "C1") (pin "1") (pinfunction "1_1") (pintype "passive"))
      (node (ref "C10") (pin "1") (pinfunction "1_1") (pintype "passive"))
      (node (ref "C11") (pin "1") (pinfunction "1_1") (pintype "passive"))
      (node (ref "C12") (pin "1") (pinfunction "1_1") (pintype "passive"))
      (node (ref "C13") (pin "1") (pinfunction "1_1") (pintype "passive"))
      (node (ref "C14") (pin "1") (pinfunction "1_1") (pintype "passive"))
      (node (ref "C15") (pin "1") (pinfunction "1_1") (pintype "passive"))
      (node (ref "C16") (pin "1") (pinfunction "1_1") (pintype "passive"))
      (node (ref "C18") (pin "2") (pinfunction "2_2") (pintype "passive"))
      (node (ref "C2") (pin "1") (pinfunction "1_1") (pintype "passive"))
      (node (ref "C20") (pin "2") (pinfunction "2_2") (pintype "passive"))
      (node (ref "C23") (pin "1") (pinfunction "1_1") (pintype "passive"))
      (node (ref "C3") (pin "1") (pinfunction "1_1") (pintype "passive"))
      (node (ref "C4") (pin "1") (pinfunction "1_1") (pintype "passive"))
      (node (ref "C5") (pin "1") (pinfunction "1_1") (pintype "passive"))
      (node (ref "C6") (pin "1") (pinfunction "1_1") (pintype "passive"))
      (node (ref "C7") (pin "1") (pinfunction "1_1") (pintype "passive"))
      (node (ref "C8") (pin "1") (pinfunction "1_1") (pintype "passive"))
      (node (ref "C9") (pin "1") (pinfunction "1_1") (pintype "passive"))
      (node (ref "D1") (pin "1") (pinfunction "Vdd_1") (pintype "power_in"))
      (node (ref "D10") (pin "1") (pinfunction "Vdd_1") (pintype "power_in"))
      (node (ref "D11") (pin "1") (pinfunction "Vdd_1") (pintype "power_in"))
      (node (ref "D12") (pin "1") (pinfunction "Vdd_1") (pintype "power_in"))
      (node (ref "D13") (pin "1") (pinfunction "Vdd_1") (pintype "power_in"))
      (node (ref "D14") (pin "1") (pinfunction "Vdd_1") (pintype "power_in"))
      (node (ref "D15") (pin "1") (pinfunction "Vdd_1") (pintype "power_in"))
      (node (ref "D2") (pin "1") (pinfunction "Vdd_1") (pintype "power_in"))
      (node (ref "D3") (pin "1") (pinfunction "Vdd_1") (pintype "power_in"))
      (node (ref "D4") (pin "1") (pinfunction "Vdd_1") (pintype "power_in"))
      (node (ref "D5") (pin "1") (pinfunction "Vdd_1") (pintype "power_in"))
      (node (ref "D6") (pin "1") (pinfunction "Vdd_1") (pintype "power_in"))
      (node (ref "D7") (pin "1") (pinfunction "Vdd_1") (pintype "power_in"))
      (node (ref "D8") (pin "1") (pinfunction "Vdd_1") (pintype "power_in"))
      (node (ref "D9") (pin "1") (pinfunction "Vdd_1") (pintype "power_in"))
      (node (ref "L1") (pin "1") (pinfunction "1_1") (pintype "passive"))
      (node (ref "R10") (pin "2") (pinfunction "2_2") (pintype "passive"))
      (node (ref "R3") (pin "2") (pinfunction "2_2") (pintype "passive"))
      (node (ref "R4") (pin "2") (pinfunction "2_2") (pintype "passive"))
      (node (ref "R6") (pin "2") (pinfunction "2_2") (pintype "passive"))
      (node (ref "U1") (pin "3") (pinfunction "VCC_3") (pintype "power_in"))
      (node (ref "U3") (pin "1") (pinfunction "VIN_1") (pintype "power_in"))
      (node (ref "U3") (pin "3") (pinfunction "EN_3") (pintype "input"))
    )
    (net (code "47") (name "Vin") (class "Default")
      (node (ref "C17") (pin "1") (pinfunction "1_1") (pintype "passive"))
      (node (ref "C19") (pin "1") (pinfunction "1_1") (pintype "passive"))
      (node (ref "CAN1") (pin "1") (pinfunction "1_1") (pintype "passive"))
      (node (ref "CAN1") (pin "2") (pinfunction "2_2") (pintype "passive"))
      (node (ref "CAN2") (pin "1") (pinfunction "1_1") (pintype "passive"))
      (node (ref "CAN2") (pin "2") (pinfunction "2_2") (pintype "passive"))
      (node (ref "R8") (pin "2") (pinfunction "2_2") (pintype "passive"))
      (node (ref "U2") (pin "2") (pinfunction "VIN_2") (pintype "power_in"))
    )
    (net (code "48") (name "unconnected-(DD1-PA0-WKUP-Pad7)") (class "Default")
      (node (ref "DD1") (pin "7") (pinfunction "PA0-WKUP_7") (pintype "bidirectional"))
    )
    (net (code "49") (name "unconnected-(DD1-PA2-Pad9)") (class "Default")
      (node (ref "DD1") (pin "9") (pinfunction "PA2_9") (pintype "bidirectional"))
    )
    (net (code "50") (name "unconnected-(DD1-PA3-Pad10)") (class "Default")
      (node (ref "DD1") (pin "10") (pinfunction "PA3_10") (pintype "bidirectional"))
    )
    (net (code "51") (name "unconnected-(DD1-PA8-Pad20)") (class "Default")
      (node (ref "DD1") (pin "20") (pinfunction "PA8_20") (pintype "bidirectional"))
    )
    (net (code "52") (name "unconnected-(DD1-PA9-Pad21)") (class "Default")
      (node (ref "DD1") (pin "21") (pinfunction "PA9_21") (pintype "bidirectional"))
    )
    (net (code "53") (name "unconnected-(DD1-PA10-Pad22)") (class "Default")
      (node (ref "DD1") (pin "22") (pinfunction "PA10_22") (pintype "bidirectional"))
    )
    (net (code "54") (name "unconnected-(R11-Pad1)") (class "Default")
      (node (ref "R11") (pin "1") (pinfunction "1_1") (pintype "passive"))
    )
    (net (code "55") (name "unconnected-(SWD1-SHIELD-PadS1)") (class "Default")
      (node (ref "SWD1") (pin "S1") (pinfunction "SHIELD_S1") (pintype "passive"))
    )
    (net (code "56") (name "unconnected-(SWD1-SHIELD-PadS2)") (class "Default")
      (node (ref "SWD1") (pin "S2") (pinfunction "SHIELD_S2") (pintype "passive"))
    )
    (net (code "57") (name "unconnected-(U2-EN-Pad3)") (class "Default")
      (node (ref "U2") (pin "3") (pinfunction "EN_3") (pintype "input"))
    )
    (net (code "58") (name "unconnected-(U3-ADJ{slash}BYP-Pad4)") (class "Default")
      (node (ref "U3") (pin "4") (pinfunction "ADJ/BYP_4") (pintype "passive"))
    )
  )
)
